# Sheet1.net
KiCad netlist of a schematic drawn in Altium Designer
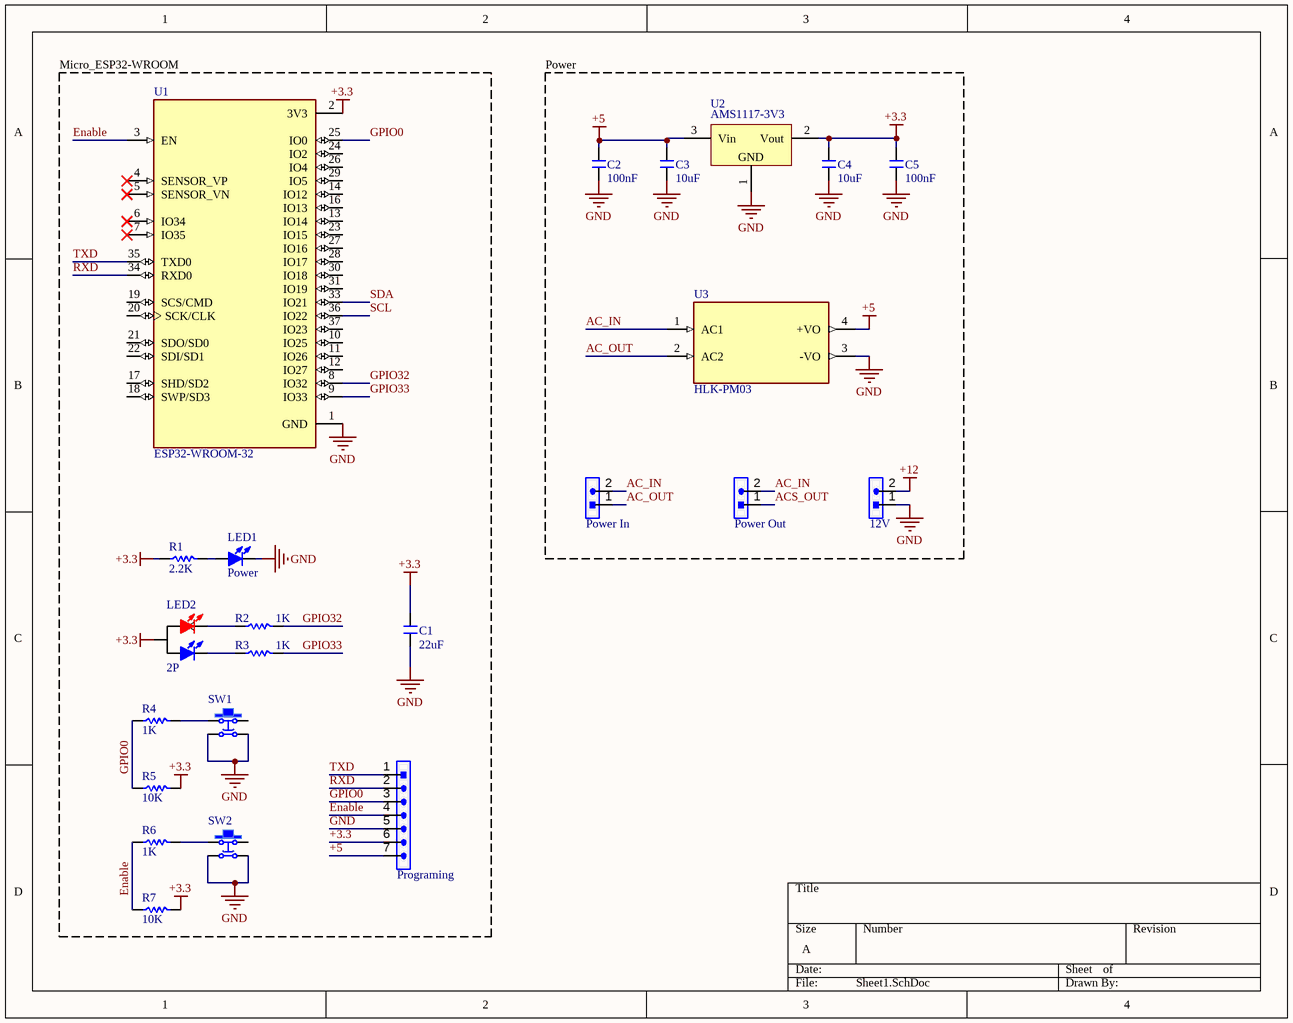
[diagram p0: Sheet1.SchDoc]

(export (version "E")
  (design (tool "Eeschema 10.0.6"))
  (components
    (comp (ref "12V")
      (value "HDR-1X2")
      (footprint "KF301-2P")
      (description "2P Connector")
      (fields (field (name "版权归属") "源创客"))
      (libsource (lib "Connectors") (part "Header 2"))
    )
    (comp (ref "C1")
      (value "22uF")
      (footprint "C 0805")
      (description "Non-polar patch capacitor")
      (fields (field (name "版权归属") "源创客"))
      (libsource (lib "Passive (Resistor-Capacitor-Inductor-Veristor-Ferrite)") (part "C"))
    )
    (comp (ref "C2")
      (value "100nF")
      (footprint "C 0805")
      (description "Non-polar patch capacitor")
      (fields (field (name "版权归属") "源创客"))
      (libsource (lib "Passive (Resistor-Capacitor-Inductor-Veristor-Ferrite)") (part "C"))
    )
    (comp (ref "C3")
      (value "10uF")
      (footprint "C 0805")
      (description "Non-polar patch capacitor")
      (fields (field (name "版权归属") "源创客"))
      (libsource (lib "Passive (Resistor-Capacitor-Inductor-Veristor-Ferrite)") (part "C"))
    )
    (comp (ref "C4")
      (value "10uF")
      (footprint "C 0805")
      (description "Non-polar patch capacitor")
      (fields (field (name "版权归属") "源创客"))
      (libsource (lib "Passive (Resistor-Capacitor-Inductor-Veristor-Ferrite)") (part "C"))
    )
    (comp (ref "C5")
      (value "100nF")
      (footprint "C 0805")
      (description "Non-polar patch capacitor")
      (fields (field (name "版权归属") "源创客"))
      (libsource (lib "Passive (Resistor-Capacitor-Inductor-Veristor-Ferrite)") (part "C"))
    )
    (comp (ref "LED1")
      (value "Power")
      (footprint "LED 0805R")
      (description "RED LED")
      (fields (field (name "版权归属") "源创客"))
      (libsource (lib "LED") (part "LED-SMD"))
    )
    (comp (ref "LED2")
      (value "2P")
      (footprint "LED 3mm-2P")
      (description "two-color LED Anode")
      (fields (field (name "版权归属") "源创客"))
      (libsource (lib "LED") (part "LED RG-A"))
    )
    (comp (ref "Power In")
      (value "HDR-1X2")
      (footprint "KF301-2P")
      (description "2P Connector")
      (fields (field (name "版权归属") "源创客"))
      (libsource (lib "Connectors") (part "Header 2"))
    )
    (comp (ref "Power Out")
      (value "HDR-1X2")
      (footprint "KF301-2P")
      (description "2P Connector")
      (fields (field (name "版权归属") "源创客"))
      (libsource (lib "Connectors") (part "Header 2"))
    )
    (comp (ref "Programing")
      (value "HDR-1X7")
      (footprint "HDR-1X7")
      (description "7P Connector")
      (fields (field (name "版权归属") "源创客"))
      (libsource (lib "Connectors") (part "Header 7"))
    )
    (comp (ref "R1")
      (value "2.2K")
      (footprint "R 0805")
      (description "Chip resistor")
      (fields (field (name "版权归属") "源创客"))
      (libsource (lib "Passive (Resistor-Capacitor-Inductor-Veristor-Ferrite)") (part "R"))
    )
    (comp (ref "R2")
      (value "1K")
      (footprint "R 0805")
      (description "Chip resistor")
      (fields (field (name "版权归属") "源创客"))
      (libsource (lib "Passive (Resistor-Capacitor-Inductor-Veristor-Ferrite)") (part "R"))
    )
    (comp (ref "R3")
      (value "1K")
      (footprint "R 0805")
      (description "Chip resistor")
      (fields (field (name "版权归属") "源创客"))
      (libsource (lib "Passive (Resistor-Capacitor-Inductor-Veristor-Ferrite)") (part "R"))
    )
    (comp (ref "R4")
      (value "1K")
      (footprint "R 0805")
      (description "Chip resistor")
      (fields (field (name "版权归属") "源创客"))
      (libsource (lib "Passive (Resistor-Capacitor-Inductor-Veristor-Ferrite)") (part "R"))
    )
    (comp (ref "R5")
      (value "10K")
      (footprint "R 0805")
      (description "Chip resistor")
      (fields (field (name "版权归属") "源创客"))
      (libsource (lib "Passive (Resistor-Capacitor-Inductor-Veristor-Ferrite)") (part "R"))
    )
    (comp (ref "R6")
      (value "1K")
      (footprint "R 0805")
      (description "Chip resistor")
      (fields (field (name "版权归属") "源创客"))
      (libsource (lib "Passive (Resistor-Capacitor-Inductor-Veristor-Ferrite)") (part "R"))
    )
    (comp (ref "R7")
      (value "10K")
      (footprint "R 0805")
      (description "Chip resistor")
      (fields (field (name "版权归属") "源创客"))
      (libsource (lib "Passive (Resistor-Capacitor-Inductor-Veristor-Ferrite)") (part "R"))
    )
    (comp (ref "SW1")
      (value "6x6x5")
      (footprint "TSW DIP-6*6*11")
      (description "Straight plug 6x6 tact switch")
      (fields (field (name "版权归属") "源创客"))
      (libsource (lib "Button") (part "TSW DIP-6x6"))
    )
    (comp (ref "SW2")
      (value "6x6x5")
      (footprint "TSW DIP-6*6*11")
      (description "Straight plug 6x6 tact switch")
      (fields (field (name "版权归属") "源创客"))
      (libsource (lib "Button") (part "TSW DIP-6x6"))
    )
    (comp (ref "U1")
      (value "ESP32-WROOM-32")
      (footprint "MODULE_ESP32-WROOM-32")
      (description "Bluetooth, WiFi Transceiver Module 2.4GHz ~ 2.5GHz Surface Mount")
      (fields (field (name "MF") "Espressif Systems") (field (name "DIGI-KEY_PART_NUMBER") "1904-1010-1-ND"))
      (libsource (lib "ESP32-WROOM-32") (part "ESP32-WROOM-32"))
    )
    (comp (ref "U2")
      (value "AMS1117-3V3")
      (footprint "SOT223_L")
      (description "Three-terminal regulator chip")
      (fields (field (name "版权归属") "源创客"))
      (libsource (lib "Integrated Circuit") (part "AMS1117"))
    )
    (comp (ref "U3")
      (value "HLK-PM03")
      (footprint "CONV_HLK-PM03")
      (description "AC DC 3W power module")
      (fields
        (field (name "MF") "Hi-link")
        (field (name "BUYPART") "https://www.snapeda.com/parts/HLK-PM03/Hi-link/view-part/3215695/?ref=eda")
      )
      (libsource (lib "HLK-PM03") (part "HLK-PM03"))
    )
  )
  (nets
    (net (code "1") (name "+3.3") (class "Default")
      (node (ref "C1") (pin "1") (pinfunction "1_1") (pintype "passive"))
      (node (ref "C4") (pin "2") (pinfunction "2_2") (pintype "passive"))
      (node (ref "C5") (pin "2") (pinfunction "2_2") (pintype "passive"))
      (node (ref "LED2") (pin "1") (pinfunction "1_1") (pintype "passive"))
      (node (ref "Programing") (pin "6") (pintype "passive"))
      (node (ref "R1") (pin "1") (pinfunction "1_1") (pintype "passive"))
      (node (ref "R5") (pin "2") (pinfunction "2_2") (pintype "passive"))
      (node (ref "R7") (pin "2") (pinfunction "2_2") (pintype "passive"))
      (node (ref "U1") (pin "2") (pinfunction "3V3_2") (pintype "power_in"))
      (node (ref "U2") (pin "2") (pinfunction "Vout_2") (pintype "passive"))
    )
    (net (code "2") (name "+5") (class "Default")
      (node (ref "C2") (pin "2") (pinfunction "2_2") (pintype "passive"))
      (node (ref "C3") (pin "2") (pinfunction "2_2") (pintype "passive"))
      (node (ref "Programing") (pin "7") (pintype "passive"))
      (node (ref "U2") (pin "3") (pinfunction "Vin_3") (pintype "passive"))
      (node (ref "U3") (pin "4") (pinfunction "+VO_4") (pintype "output"))
    )
    (net (code "3") (name "+12") (class "Default") (node (ref "12V") (pin "2") (pintype "passive")))
    (net (code "4") (name "/ACS_OUT") (class "Default")
      (node (ref "Power Out") (pin "1") (pintype "passive"))
    )
    (net (code "5") (name "/AC_IN") (class "Default")
      (node (ref "Power In") (pin "2") (pintype "passive"))
      (node (ref "Power Out") (pin "2") (pintype "passive"))
      (node (ref "U3") (pin "1") (pinfunction "AC1_1") (pintype "input"))
    )
    (net (code "6") (name "/AC_OUT") (class "Default")
      (node (ref "Power In") (pin "1") (pintype "passive"))
      (node (ref "U3") (pin "2") (pinfunction "AC2_2") (pintype "input"))
    )
    (net (code "7") (name "/Enable") (class "Default")
      (node (ref "Programing") (pin "4") (pintype "passive"))
      (node (ref "R6") (pin "1") (pinfunction "1_1") (pintype "passive"))
      (node (ref "R7") (pin "1") (pinfunction "1_1") (pintype "passive"))
      (node (ref "U1") (pin "3") (pinfunction "EN_3") (pintype "input"))
    )
    (net (code "8") (name "/GPIO0") (class "Default")
      (node (ref "Programing") (pin "3") (pintype "passive"))
      (node (ref "R4") (pin "1") (pinfunction "1_1") (pintype "passive"))
      (node (ref "R5") (pin "1") (pinfunction "1_1") (pintype "passive"))
      (node (ref "U1") (pin "25") (pinfunction "IO0_25") (pintype "bidirectional"))
    )
    (net (code "9") (name "/GPIO32") (class "Default")
      (node (ref "R2") (pin "2") (pinfunction "2_2") (pintype "passive"))
      (node (ref "U1") (pin "8") (pinfunction "IO32_8") (pintype "bidirectional"))
    )
    (net (code "10") (name "/GPIO33") (class "Default")
      (node (ref "R3") (pin "2") (pinfunction "2_2") (pintype "passive"))
      (node (ref "U1") (pin "9") (pinfunction "IO33_9") (pintype "bidirectional"))
    )
    (net (code "11") (name "/RXD") (class "Default")
      (node (ref "Programing") (pin "2") (pintype "passive"))
      (node (ref "U1") (pin "34") (pinfunction "RXD0_34") (pintype "bidirectional"))
    )
    (net (code "12") (name "/SCL") (class "Default")
      (node (ref "U1") (pin "36") (pinfunction "IO22_36") (pintype "bidirectional"))
    )
    (net (code "13") (name "/SDA") (class "Default")
      (node (ref "U1") (pin "33") (pinfunction "IO21_33") (pintype "bidirectional"))
    )
    (net (code "14") (name "/TXD") (class "Default")
      (node (ref "Programing") (pin "1") (pintype "passive"))
      (node (ref "U1") (pin "35") (pinfunction "TXD0_35") (pintype "bidirectional"))
    )
    (net (code "15") (name "GND") (class "Default")
      (node (ref "12V") (pin "1") (pintype "passive"))
      (node (ref "C1") (pin "2") (pinfunction "2_2") (pintype "passive"))
      (node (ref "C2") (pin "1") (pinfunction "1_1") (pintype "passive"))
      (node (ref "C3") (pin "1") (pinfunction "1_1") (pintype "passive"))
      (node (ref "C4") (pin "1") (pinfunction "1_1") (pintype "passive"))
      (node (ref "C5") (pin "1") (pinfunction "1_1") (pintype "passive"))
      (node (ref "LED1") (pin "2") (pinfunction "K_2") (pintype "passive"))
      (node (ref "Programing") (pin "5") (pintype "passive"))
      (node (ref "SW1") (pin "2") (pinfunction "2_2") (pintype "passive"))
      (node (ref "SW1") (pin "3") (pinfunction "3_3") (pintype "passive"))
      (node (ref "SW2") (pin "2") (pinfunction "2_2") (pintype "passive"))
      (node (ref "SW2") (pin "3") (pinfunction "3_3") (pintype "passive"))
      (node (ref "U1") (pin "1") (pinfunction "GND_1") (pintype "power_in"))
      (node (ref "U2") (pin "1") (pinfunction "GND_1") (pintype "passive"))
      (node (ref "U3") (pin "3") (pinfunction "-VO_3") (pintype "output"))
    )
    (net (code "16") (name "Net-(LED1-A)") (class "Default")
      (node (ref "LED1") (pin "1") (pinfunction "A_1") (pintype "passive"))
      (node (ref "R1") (pin "2") (pinfunction "2_2") (pintype "passive"))
    )
    (net (code "17") (name "Net-(LED2-Pad2)") (class "Default")
      (node (ref "LED2") (pin "2") (pinfunction "2_2") (pintype "passive"))
      (node (ref "R2") (pin "1") (pinfunction "1_1") (pintype "passive"))
    )
    (net (code "18") (name "Net-(LED2-Pad3)") (class "Default")
      (node (ref "LED2") (pin "3") (pinfunction "3_3") (pintype "passive"))
      (node (ref "R3") (pin "1") (pinfunction "1_1") (pintype "passive"))
    )
    (net (code "19") (name "Net-(R4-Pad2)") (class "Default")
      (node (ref "R4") (pin "2") (pinfunction "2_2") (pintype "passive"))
      (node (ref "SW1") (pin "1") (pinfunction "1_1") (pintype "passive"))
    )
    (net (code "20") (name "Net-(R6-Pad2)") (class "Default")
      (node (ref "R6") (pin "2") (pinfunction "2_2") (pintype "passive"))
      (node (ref "SW2") (pin "1") (pinfunction "1_1") (pintype "passive"))
    )
    (net (code "21") (name "unconnected-(SW1-Pad4)") (class "Default")
      (node (ref "SW1") (pin "4") (pinfunction "4_4") (pintype "passive"))
    )
    (net (code "22") (name "unconnected-(SW2-Pad4)") (class "Default")
      (node (ref "SW2") (pin "4") (pinfunction "4_4") (pintype "passive"))
    )
    (net (code "23") (name "unconnected-(U1-IO2-Pad24)") (class "Default")
      (node (ref "U1") (pin "24") (pinfunction "IO2_24") (pintype "bidirectional"))
    )
    (net (code "24") (name "unconnected-(U1-IO4-Pad26)") (class "Default")
      (node (ref "U1") (pin "26") (pinfunction "IO4_26") (pintype "bidirectional"))
    )
    (net (code "25") (name "unconnected-(U1-IO5-Pad29)") (class "Default")
      (node (ref "U1") (pin "29") (pinfunction "IO5_29") (pintype "bidirectional"))
    )
    (net (code "26") (name "unconnected-(U1-IO12-Pad14)") (class "Default")
      (node (ref "U1") (pin "14") (pinfunction "IO12_14") (pintype "bidirectional"))
    )
    (net (code "27") (name "unconnected-(U1-IO13-Pad16)") (class "Default")
      (node (ref "U1") (pin "16") (pinfunction "IO13_16") (pintype "bidirectional"))
    )
    (net (code "28") (name "unconnected-(U1-IO14-Pad13)") (class "Default")
      (node (ref "U1") (pin "13") (pinfunction "IO14_13") (pintype "bidirectional"))
    )
    (net (code "29") (name "unconnected-(U1-IO15-Pad23)") (class "Default")
      (node (ref "U1") (pin "23") (pinfunction "IO15_23") (pintype "bidirectional"))
    )
    (net (code "30") (name "unconnected-(U1-IO16-Pad27)") (class "Default")
      (node (ref "U1") (pin "27") (pinfunction "IO16_27") (pintype "bidirectional"))
    )
    (net (code "31") (name "unconnected-(U1-IO17-Pad28)") (class "Default")
      (node (ref "U1") (pin "28") (pinfunction "IO17_28") (pintype "bidirectional"))
    )
    (net (code "32") (name "unconnected-(U1-IO18-Pad30)") (class "Default")
      (node (ref "U1") (pin "30") (pinfunction "IO18_30") (pintype "bidirectional"))
    )
    (net (code "33") (name "unconnected-(U1-IO19-Pad31)") (class "Default")
      (node (ref "U1") (pin "31") (pinfunction "IO19_31") (pintype "bidirectional"))
    )
    (net (code "34") (name "unconnected-(U1-IO23-Pad37)") (class "Default")
      (node (ref "U1") (pin "37") (pinfunction "IO23_37") (pintype "bidirectional"))
    )
    (net (code "35") (name "unconnected-(U1-IO25-Pad10)") (class "Default")
      (node (ref "U1") (pin "10") (pinfunction "IO25_10") (pintype "bidirectional"))
    )
    (net (code "36") (name "unconnected-(U1-IO26-Pad11)") (class "Default")
      (node (ref "U1") (pin "11") (pinfunction "IO26_11") (pintype "bidirectional"))
    )
    (net (code "37") (name "unconnected-(U1-IO27-Pad12)") (class "Default")
      (node (ref "U1") (pin "12") (pinfunction "IO27_12") (pintype "bidirectional"))
    )
    (net (code "38") (name "unconnected-(U1-IO34-Pad6)") (class "Default")
      (node (ref "U1") (pin "6") (pinfunction "IO34_6") (pintype "input+no_connect"))
    )
    (net (code "39") (name "unconnected-(U1-IO35-Pad7)") (class "Default")
      (node (ref "U1") (pin "7") (pinfunction "IO35_7") (pintype "input+no_connect"))
    )
    (net (code "40") (name "unconnected-(U1-SCK{slash}CLK-Pad20)") (class "Default")
      (node (ref "U1") (pin "20") (pinfunction "SCK/CLK_20") (pintype "bidirectional"))
    )
    (net (code "41") (name "unconnected-(U1-SCS{slash}CMD-Pad19)") (class "Default")
      (node (ref "U1") (pin "19") (pinfunction "SCS/CMD_19") (pintype "bidirectional"))
    )
    (net (code "42") (name "unconnected-(U1-SDI{slash}SD1-Pad22)") (class "Default")
      (node (ref "U1") (pin "22") (pinfunction "SDI/SD1_22") (pintype "bidirectional"))
    )
    (net (code "43") (name "unconnected-(U1-SDO{slash}SD0-Pad21)") (class "Default")
      (node (ref "U1") (pin "21") (pinfunction "SDO/SD0_21") (pintype "bidirectional"))
    )
    (net (code "44") (name "unconnected-(U1-SENSOR_VN-Pad5)") (class "Default")
      (node (ref "U1") (pin "5") (pinfunction "SENSOR_VN_5") (pintype "input+no_connect"))
    )
    (net (code "45") (name "unconnected-(U1-SENSOR_VP-Pad4)") (class "Default")
      (node (ref "U1") (pin "4") (pinfunction "SENSOR_VP_4") (pintype "input+no_connect"))
    )
    (net (code "46") (name "unconnected-(U1-SHD{slash}SD2-Pad17)") (class "Default")
      (node (ref "U1") (pin "17") (pinfunction "SHD/SD2_17") (pintype "bidirectional"))
    )
    (net (code "47") (name "unconnected-(U1-SWP{slash}SD3-Pad18)") (class "Default")
      (node (ref "U1") (pin "18") (pinfunction "SWP/SD3_18") (pintype "bidirectional"))
    )
  )
)
